# esquematico_projeto-integrado2TRI.net
KiCad netlist of a schematic drawn in EAGLE
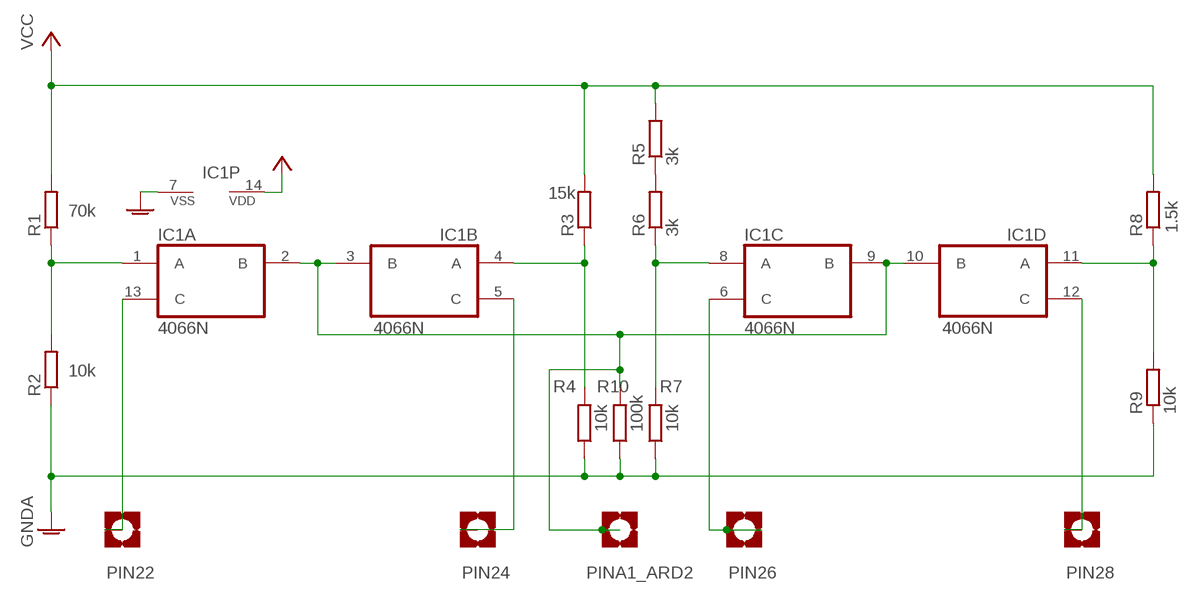
[diagram p0: schematic, sheet 1]

(export (version "E")
  (design (tool "Eeschema 10.0.6"))
  (components
    (comp (ref "IC1")
      (value "4066N")
      (footprint "eagle-import:DIL14")
      (fields (field (name "SPICEPREFIX") "J"))
      (libsource (lib "eagle-import") (part "4066N"))
    )
    (comp (ref "PIN22")
      (value "MOUNT-PAD-SQUARE2.8")
      (footprint "eagle-import:2,8-PAD-SQUARE")
      (libsource (lib "eagle-import") (part "MOUNT-PAD-SQUARE2.8"))
    )
    (comp (ref "PIN24")
      (value "MOUNT-PAD-SQUARE2.8")
      (footprint "eagle-import:2,8-PAD-SQUARE")
      (libsource (lib "eagle-import") (part "MOUNT-PAD-SQUARE2.8"))
    )
    (comp (ref "PIN26")
      (value "MOUNT-PAD-SQUARE2.8")
      (footprint "eagle-import:2,8-PAD-SQUARE")
      (libsource (lib "eagle-import") (part "MOUNT-PAD-SQUARE2.8"))
    )
    (comp (ref "PIN28")
      (value "MOUNT-PAD-SQUARE2.8")
      (footprint "eagle-import:2,8-PAD-SQUARE")
      (libsource (lib "eagle-import") (part "MOUNT-PAD-SQUARE2.8"))
    )
    (comp (ref "PINA1_ARD2")
      (value "MOUNT-PAD-SQUARE2.8")
      (footprint "eagle-import:2,8-PAD-SQUARE")
      (libsource (lib "eagle-import") (part "MOUNT-PAD-SQUARE2.8"))
    )
    (comp (ref "R1")
      (value "70k")
      (footprint "eagle-import:0309_10")
      (libsource (lib "eagle-import") (part "R-EU_0309/10"))
    )
    (comp (ref "R2")
      (value "10k")
      (footprint "eagle-import:0309_10")
      (libsource (lib "eagle-import") (part "R-EU_0309/10"))
    )
    (comp (ref "R3")
      (value "15k")
      (footprint "eagle-import:0309_10")
      (libsource (lib "eagle-import") (part "R-EU_0309/10"))
    )
    (comp (ref "R4")
      (value "10k")
      (footprint "eagle-import:0309_10")
      (libsource (lib "eagle-import") (part "R-EU_0309/10"))
    )
    (comp (ref "R5")
      (value "3k")
      (footprint "eagle-import:0309_10")
      (libsource (lib "eagle-import") (part "R-EU_0309/10"))
    )
    (comp (ref "R6")
      (value "3k")
      (footprint "eagle-import:0309_10")
      (libsource (lib "eagle-import") (part "R-EU_0309/10"))
    )
    (comp (ref "R7")
      (value "10k")
      (footprint "eagle-import:0309_10")
      (libsource (lib "eagle-import") (part "R-EU_0309/10"))
    )
    (comp (ref "R8")
      (value "1.5k")
      (footprint "eagle-import:0309_10")
      (libsource (lib "eagle-import") (part "R-EU_0309/10"))
    )
    (comp (ref "R9")
      (value "10k")
      (footprint "eagle-import:0309_10")
      (libsource (lib "eagle-import") (part "R-EU_0309/10"))
    )
    (comp (ref "R10")
      (value "100k")
      (footprint "eagle-import:0309_10")
      (libsource (lib "eagle-import") (part "R-EU_0309/10"))
    )
  )
  (nets
    (net (code "1") (name "GNDA") (class "Default")
      (node (ref "IC1") (pin "7") (pinfunction "VSS_7") (pintype "power_in"))
      (node (ref "R10") (pin "1") (pinfunction "1_1") (pintype "passive"))
      (node (ref "R2") (pin "1") (pinfunction "1_1") (pintype "passive"))
      (node (ref "R4") (pin "1") (pinfunction "1_1") (pintype "passive"))
      (node (ref "R7") (pin "1") (pinfunction "1_1") (pintype "passive"))
      (node (ref "R9") (pin "1") (pinfunction "1_1") (pintype "passive"))
    )
    (net (code "2") (name "Net-(IC1A-A)") (class "Default")
      (node (ref "IC1") (pin "1") (pinfunction "A_1") (pintype "tri_state"))
      (node (ref "R1") (pin "1") (pinfunction "1_1") (pintype "passive"))
      (node (ref "R2") (pin "2") (pinfunction "2_2") (pintype "passive"))
    )
    (net (code "3") (name "Net-(IC1A-B)") (class "Default")
      (node (ref "IC1") (pin "10") (pinfunction "B_10") (pintype "tri_state"))
      (node (ref "IC1") (pin "2") (pinfunction "B_2") (pintype "tri_state"))
      (node (ref "IC1") (pin "3") (pinfunction "B_3") (pintype "tri_state"))
      (node (ref "IC1") (pin "9") (pinfunction "B_9") (pintype "tri_state"))
      (node (ref "PINA1_ARD2") (pin "B2,8") (pinfunction "MOUNT_B2,8") (pintype "passive"))
      (node (ref "R10") (pin "2") (pinfunction "2_2") (pintype "passive"))
    )
    (net (code "4") (name "Net-(IC1A-C)") (class "Default")
      (node (ref "IC1") (pin "13") (pinfunction "C_13") (pintype "input"))
      (node (ref "PIN22") (pin "B2,8") (pinfunction "MOUNT_B2,8") (pintype "passive"))
    )
    (net (code "5") (name "Net-(IC1B-A)") (class "Default")
      (node (ref "IC1") (pin "4") (pinfunction "A_4") (pintype "tri_state"))
      (node (ref "R3") (pin "1") (pinfunction "1_1") (pintype "passive"))
      (node (ref "R4") (pin "2") (pinfunction "2_2") (pintype "passive"))
    )
    (net (code "6") (name "Net-(IC1B-C)") (class "Default")
      (node (ref "IC1") (pin "5") (pinfunction "C_5") (pintype "input"))
      (node (ref "PIN24") (pin "B2,8") (pinfunction "MOUNT_B2,8") (pintype "passive"))
    )
    (net (code "7") (name "Net-(IC1C-A)") (class "Default")
      (node (ref "IC1") (pin "8") (pinfunction "A_8") (pintype "tri_state"))
      (node (ref "R6") (pin "1") (pinfunction "1_1") (pintype "passive"))
      (node (ref "R7") (pin "2") (pinfunction "2_2") (pintype "passive"))
    )
    (net (code "8") (name "Net-(IC1C-C)") (class "Default")
      (node (ref "IC1") (pin "6") (pinfunction "C_6") (pintype "input"))
      (node (ref "PIN26") (pin "B2,8") (pinfunction "MOUNT_B2,8") (pintype "passive"))
    )
    (net (code "9") (name "Net-(IC1D-A)") (class "Default")
      (node (ref "IC1") (pin "11") (pinfunction "A_11") (pintype "tri_state"))
      (node (ref "R8") (pin "1") (pinfunction "1_1") (pintype "passive"))
      (node (ref "R9") (pin "2") (pinfunction "2_2") (pintype "passive"))
    )
    (net (code "10") (name "Net-(IC1D-C)") (class "Default")
      (node (ref "IC1") (pin "12") (pinfunction "C_12") (pintype "input"))
      (node (ref "PIN28") (pin "B2,8") (pinfunction "MOUNT_B2,8") (pintype "passive"))
    )
    (net (code "11") (name "Net-(R5-Pad1)") (class "Default")
      (node (ref "R5") (pin "1") (pinfunction "1_1") (pintype "passive"))
      (node (ref "R6") (pin "2") (pinfunction "2_2") (pintype "passive"))
    )
    (net (code "12") (name "VCC") (class "Default")
      (node (ref "IC1") (pin "14") (pinfunction "VDD_14") (pintype "power_in"))
      (node (ref "R1") (pin "2") (pinfunction "2_2") (pintype "passive"))
      (node (ref "R3") (pin "2") (pinfunction "2_2") (pintype "passive"))
      (node (ref "R5") (pin "2") (pinfunction "2_2") (pintype "passive"))
      (node (ref "R8") (pin "2") (pinfunction "2_2") (pintype "passive"))
    )
  )
)
